# mpuhand2.net
KiCad netlist of a schematic drawn in Altium Designer
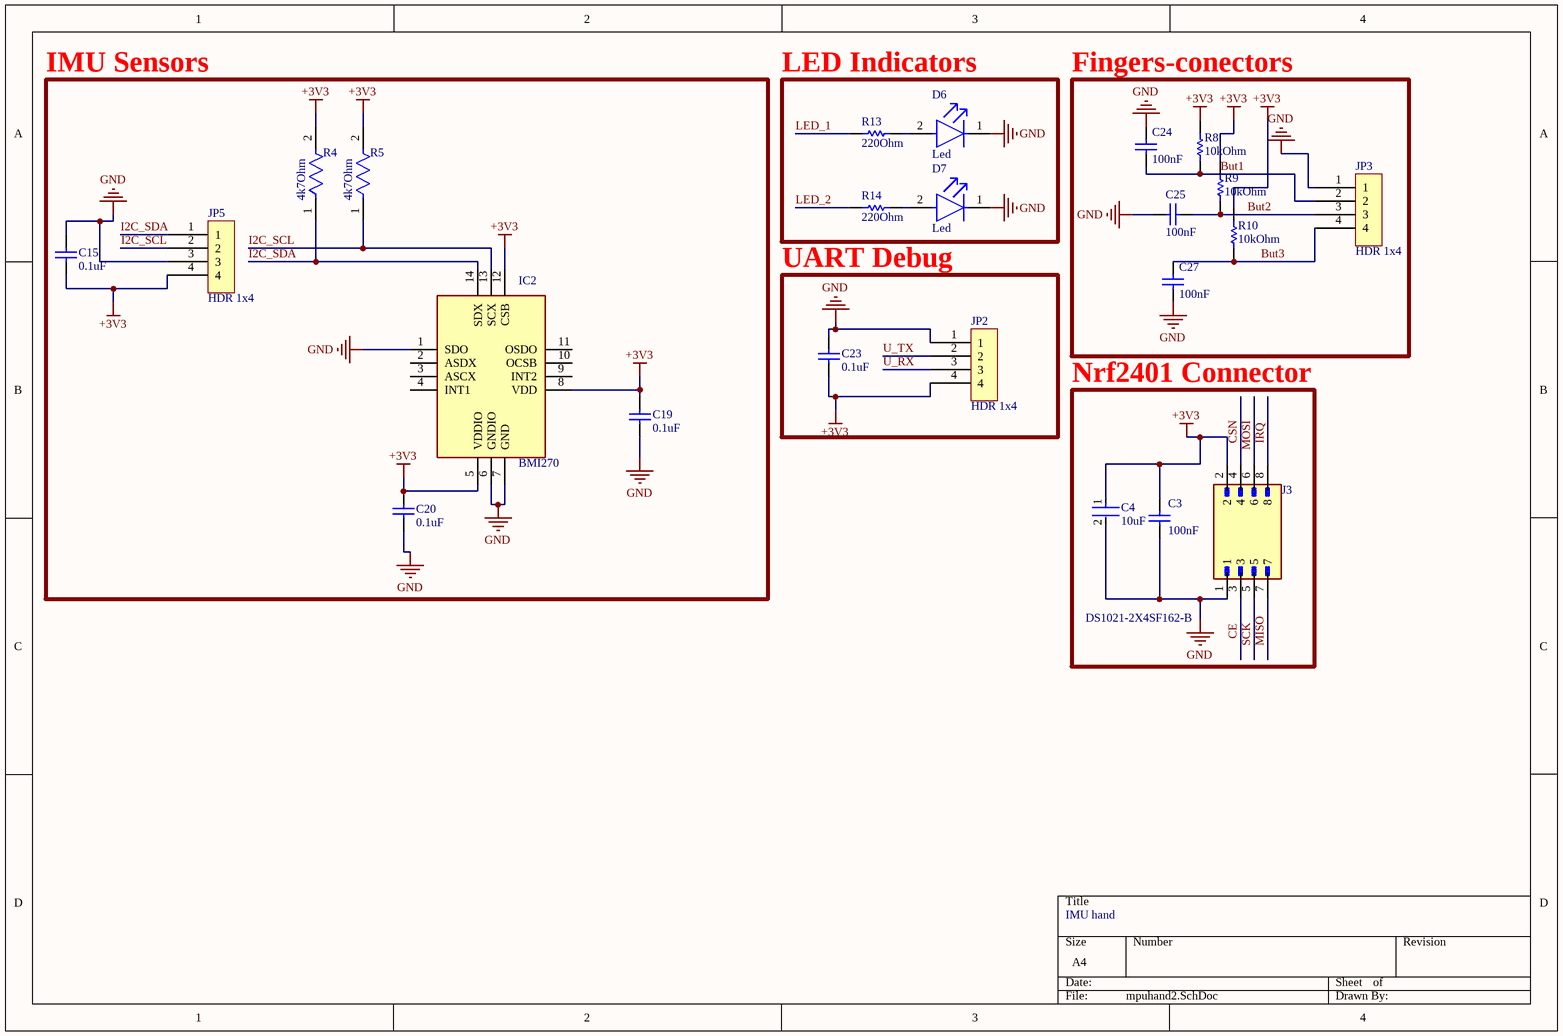
[diagram p0: mpuhand2.SchDoc]

(export (version "E")
  (design (tool "Eeschema 10.0.6"))
  (components
    (comp (ref "C3")
      (value "100nF")
      (footprint "CAPC1050X55X23ML05T13")
      (description "Chip Capacitor, 100 nF, +/- 10%, 16 V, -55 to 125 degC, 0402 (1005 Metric), RoHS, Tape and Reel")
      (fields (field (name "MANUFACTURER") "Samsung Electro-Mechanics"))
      (libsource (lib "Altium Content Vault") (part "CAP-NP-2"))
    )
    (comp (ref "C4")
      (value "10uF")
      (footprint "FP-CL21-IPC_B")
      (description "CL21 Series 0805 10uF 16V ±10% Tolerance X5R Multilayer Ceramic Chip Capacitor")
      (fields (field (name "VOLTAGE") "16V") (field (name "TOLERANCE") "10%"))
      (libsource (lib "Altium Content Vault") (part "b4654b650e69147ec39a6b967a45e02"))
    )
    (comp (ref "C15")
      (value "0.1uF")
      (footprint "CAPC1050X55X23ML05T13")
      (description "Chip Capacitor, 100 nF, +/- 10%, 16 V, -55 to 125 degC, 0402 (1005 Metric), RoHS, Tape and Reel")
      (fields (field (name "MANUFACTURER") "Samsung Electro-Mechanics"))
      (libsource (lib "Altium Content Vault") (part "CAP-NP-2"))
    )
    (comp (ref "C19")
      (value "0.1uF")
      (footprint "CAPC1050X55X23ML05T13")
      (description "Chip Capacitor, 100 nF, +/- 10%, 16 V, -55 to 125 degC, 0402 (1005 Metric), RoHS, Tape and Reel")
      (fields (field (name "MANUFACTURER") "Samsung Electro-Mechanics"))
      (libsource (lib "Altium Content Vault") (part "CAP-NP-2"))
    )
    (comp (ref "C20")
      (value "0.1uF")
      (footprint "CAPC1050X55X23ML05T13")
      (description "Chip Capacitor, 100 nF, +/- 10%, 16 V, -55 to 125 degC, 0402 (1005 Metric), RoHS, Tape and Reel")
      (fields (field (name "MANUFACTURER") "Samsung Electro-Mechanics"))
      (libsource (lib "Altium Content Vault") (part "CAP-NP-2"))
    )
    (comp (ref "C23")
      (value "0.1uF")
      (footprint "CAPC1050X55X23ML05T13")
      (description "Chip Capacitor, 100 nF, +/- 10%, 16 V, -55 to 125 degC, 0402 (1005 Metric), RoHS, Tape and Reel")
      (fields (field (name "MANUFACTURER") "Samsung Electro-Mechanics"))
      (libsource (lib "Altium Content Vault") (part "CAP-NP-2"))
    )
    (comp (ref "C24")
      (value "100nF")
      (footprint "CAPC1050X55X23ML05T13")
      (description "Chip Capacitor, 100 nF, +/- 10%, 16 V, -55 to 125 degC, 0402 (1005 Metric), RoHS, Tape and Reel")
      (fields (field (name "MANUFACTURER") "Samsung Electro-Mechanics"))
      (libsource (lib "Altium Content Vault") (part "CAP-NP-2"))
    )
    (comp (ref "C25")
      (value "100nF")
      (footprint "CAPC1050X55X23ML05T13")
      (description "Chip Capacitor, 100 nF, +/- 10%, 16 V, -55 to 125 degC, 0402 (1005 Metric), RoHS, Tape and Reel")
      (fields (field (name "MANUFACTURER") "Samsung Electro-Mechanics"))
      (libsource (lib "Altium Content Vault") (part "CAP-NP-2"))
    )
    (comp (ref "C27")
      (value "100nF")
      (footprint "CAPC1050X55X23ML05T13")
      (description "Chip Capacitor, 100 nF, +/- 10%, 16 V, -55 to 125 degC, 0402 (1005 Metric), RoHS, Tape and Reel")
      (fields (field (name "MANUFACTURER") "Samsung Electro-Mechanics"))
      (libsource (lib "Altium Content Vault") (part "CAP-NP-2"))
    )
    (comp (ref "D6")
      (value "Led")
      (footprint "FP-LTST-C191GKT-MFG")
      (description "LED GREEN CLEAR CHIP SMD")
      (libsource (lib "Altium Content Vault") (part "8706943c75ba83719d021d2fdc84c58"))
    )
    (comp (ref "D7")
      (value "Led")
      (footprint "FP-LTST-C191GKT-MFG")
      (description "LED GREEN CLEAR CHIP SMD")
      (libsource (lib "Altium Content Vault") (part "8706943c75ba83719d021d2fdc84c58"))
    )
    (comp (ref "IC2")
      (value "BMI270")
      (footprint "SamacSys:BMI270")
      (description "Integrated Circuit")
      (fields (field (name "MOUSER PART NUMBER") "262-BMI270"))
      (libsource (lib "*") (part "BMI270"))
    )
    (comp (ref "J3")
      (value "DS1021-2X4SF162-B")
      (footprint "CONNFLY_DS1021-2X4SF162-B")
      (description "Pin header; pin strips; male; PIN: 8; straight; 2.54mm; THT; 2x4")
      (fields (field (name "MF") "Connfly"))
      (libsource (lib "DS1021-2X4SF162-B") (part "DS1021-2X4SF162-B"))
    )
    (comp (ref "JP2")
      (value "HDR 1x4")
      (footprint "HDR Male1_4 2.54mm")
      (description "CONN HEADER VERT 4POS 2.54MM")
      (fields
        (field (name "MANUFACTURER") "Amphenol FCI")
        (field (name "MANUFACTURER PART NUMBER") "68001-204HLF")
      )
      (libsource (lib "Male_Header_1_4 2.54mm") (part "68001-204HLF"))
    )
    (comp (ref "JP3")
      (value "HDR 1x4")
      (footprint "HDR Male1_4 2.54mm")
      (description "CONN HEADER VERT 4POS 2.54MM")
      (fields
        (field (name "MANUFACTURER") "Amphenol FCI")
        (field (name "MANUFACTURER PART NUMBER") "68001-204HLF")
      )
      (libsource (lib "Male_Header_1_4 2.54mm") (part "68001-204HLF"))
    )
    (comp (ref "JP5")
      (value "HDR 1x4")
      (footprint "HDR Male1_4 2.54mm")
      (description "CONN HEADER VERT 4POS 2.54MM")
      (fields
        (field (name "MANUFACTURER") "Amphenol FCI")
        (field (name "MANUFACTURER PART NUMBER") "68001-204HLF")
      )
      (libsource (lib "Male_Header_1_4 2.54mm") (part "68001-204HLF"))
    )
    (comp (ref "R4")
      (value "4k7Ohm")
      (footprint "FP-RC0402-0_4-MFG")
      (fields (field (name "TOLERANCE") "5%"))
      (libsource (lib "Altium Content Vault") (part "RC0402JR-074K7L"))
    )
    (comp (ref "R5")
      (value "4k7Ohm")
      (footprint "FP-RC0402-0_4-MFG")
      (fields (field (name "TOLERANCE") "5%"))
      (libsource (lib "Altium Content Vault") (part "RC0402JR-074K7L"))
    )
    (comp (ref "R8")
      (value "10kOhm")
      (footprint "RESC2013X60X35ML10T20")
      (description "Chip Resistor, 10 KOhm, +/- 5%, 0.125 W, -55 to 155 degC, 0805 (2012 Metric), RoHS, Tape and Reel")
      (fields (field (name "MANUFACTURER") "Yageo"))
      (libsource (lib "Altium Content Vault") (part "RES-2"))
    )
    (comp (ref "R9")
      (value "10kOhm")
      (footprint "RESC2013X60X35ML10T20")
      (description "Chip Resistor, 10 KOhm, +/- 5%, 0.125 W, -55 to 155 degC, 0805 (2012 Metric), RoHS, Tape and Reel")
      (fields (field (name "MANUFACTURER") "Yageo"))
      (libsource (lib "Altium Content Vault") (part "RES-2"))
    )
    (comp (ref "R10")
      (value "10kOhm")
      (footprint "RESC2013X60X35ML10T20")
      (description "Chip Resistor, 10 KOhm, +/- 5%, 0.125 W, -55 to 155 degC, 0805 (2012 Metric), RoHS, Tape and Reel")
      (fields (field (name "MANUFACTURER") "Yageo"))
      (libsource (lib "Altium Content Vault") (part "RES-2"))
    )
    (comp (ref "R13")
      (value "220Ohm")
      (footprint "RESC1608X55X25ML10T15")
      (libsource (lib "Altium Content Vault") (part "RES-2"))
    )
    (comp (ref "R14")
      (value "220Ohm")
      (footprint "RESC1608X55X25ML10T15")
      (libsource (lib "Altium Content Vault") (part "RES-2"))
    )
  )
  (nets
    (net (code "1") (name "+3V3") (class "Default")
      (node (ref "C15") (pin "1") (pinfunction "1_1") (pintype "passive"))
      (node (ref "C19") (pin "2") (pinfunction "2_2") (pintype "passive"))
      (node (ref "C20") (pin "2") (pinfunction "2_2") (pintype "passive"))
      (node (ref "C23") (pin "1") (pinfunction "1_1") (pintype "passive"))
      (node (ref "C3") (pin "2") (pinfunction "2_2") (pintype "passive"))
      (node (ref "C4") (pin "1") (pinfunction "1_1") (pintype "passive"))
      (node (ref "IC2") (pin "12") (pinfunction "CSB_12") (pintype "passive"))
      (node (ref "IC2") (pin "5") (pinfunction "VDDIO_5") (pintype "passive"))
      (node (ref "IC2") (pin "8") (pinfunction "VDD_8") (pintype "passive"))
      (node (ref "J3") (pin "2") (pinfunction "2_2") (pintype "passive"))
      (node (ref "JP2") (pin "4") (pinfunction "4_4") (pintype "passive"))
      (node (ref "JP5") (pin "4") (pinfunction "4_4") (pintype "passive"))
      (node (ref "R10") (pin "2") (pinfunction "2_2") (pintype "passive"))
      (node (ref "R4") (pin "2") (pinfunction "2_2") (pintype "passive"))
      (node (ref "R5") (pin "2") (pinfunction "2_2") (pintype "passive"))
      (node (ref "R8") (pin "2") (pinfunction "2_2") (pintype "passive"))
      (node (ref "R9") (pin "2") (pinfunction "2_2") (pintype "passive"))
    )
    (net (code "2") (name "/But1") (class "Default")
      (node (ref "C24") (pin "1") (pinfunction "1_1") (pintype "passive"))
      (node (ref "JP3") (pin "2") (pinfunction "2_2") (pintype "passive"))
      (node (ref "R8") (pin "1") (pinfunction "1_1") (pintype "passive"))
    )
    (net (code "3") (name "/But2") (class "Default")
      (node (ref "C25") (pin "2") (pinfunction "2_2") (pintype "passive"))
      (node (ref "JP3") (pin "3") (pinfunction "3_3") (pintype "passive"))
      (node (ref "R9") (pin "1") (pinfunction "1_1") (pintype "passive"))
    )
    (net (code "4") (name "/But3") (class "Default")
      (node (ref "C27") (pin "2") (pinfunction "2_2") (pintype "passive"))
      (node (ref "JP3") (pin "4") (pinfunction "4_4") (pintype "passive"))
      (node (ref "R10") (pin "1") (pinfunction "1_1") (pintype "passive"))
    )
    (net (code "5") (name "/CE") (class "Default")
      (node (ref "J3") (pin "3") (pinfunction "3_3") (pintype "passive"))
    )
    (net (code "6") (name "/CSN") (class "Default")
      (node (ref "J3") (pin "4") (pinfunction "4_4") (pintype "passive"))
    )
    (net (code "7") (name "/I2C_SCL") (class "Default")
      (node (ref "IC2") (pin "13") (pinfunction "SCX_13") (pintype "passive"))
      (node (ref "JP5") (pin "2") (pinfunction "2_2") (pintype "passive"))
      (node (ref "R5") (pin "1") (pinfunction "1_1") (pintype "passive"))
    )
    (net (code "8") (name "/I2C_SDA") (class "Default")
      (node (ref "IC2") (pin "14") (pinfunction "SDX_14") (pintype "passive"))
      (node (ref "JP5") (pin "1") (pinfunction "1_1") (pintype "passive"))
      (node (ref "R4") (pin "1") (pinfunction "1_1") (pintype "passive"))
    )
    (net (code "9") (name "/IRQ") (class "Default")
      (node (ref "J3") (pin "8") (pinfunction "8_8") (pintype "passive"))
    )
    (net (code "10") (name "/LED_1") (class "Default")
      (node (ref "R13") (pin "2") (pinfunction "2_2") (pintype "passive"))
    )
    (net (code "11") (name "/LED_2") (class "Default")
      (node (ref "R14") (pin "2") (pinfunction "2_2") (pintype "passive"))
    )
    (net (code "12") (name "/MISO") (class "Default")
      (node (ref "J3") (pin "7") (pinfunction "7_7") (pintype "passive"))
    )
    (net (code "13") (name "/MOSI") (class "Default")
      (node (ref "J3") (pin "6") (pinfunction "6_6") (pintype "passive"))
    )
    (net (code "14") (name "/SCK") (class "Default")
      (node (ref "J3") (pin "5") (pinfunction "5_5") (pintype "passive"))
    )
    (net (code "15") (name "/U_RX") (class "Default")
      (node (ref "JP2") (pin "3") (pinfunction "3_3") (pintype "passive"))
    )
    (net (code "16") (name "/U_TX") (class "Default")
      (node (ref "JP2") (pin "2") (pinfunction "2_2") (pintype "passive"))
    )
    (net (code "17") (name "GND") (class "Default")
      (node (ref "C15") (pin "2") (pinfunction "2_2") (pintype "passive"))
      (node (ref "C19") (pin "1") (pinfunction "1_1") (pintype "passive"))
      (node (ref "C20") (pin "1") (pinfunction "1_1") (pintype "passive"))
      (node (ref "C23") (pin "2") (pinfunction "2_2") (pintype "passive"))
      (node (ref "C24") (pin "2") (pinfunction "2_2") (pintype "passive"))
      (node (ref "C25") (pin "1") (pinfunction "1_1") (pintype "passive"))
      (node (ref "C27") (pin "1") (pinfunction "1_1") (pintype "passive"))
      (node (ref "C3") (pin "1") (pinfunction "1_1") (pintype "passive"))
      (node (ref "C4") (pin "2") (pinfunction "2_2") (pintype "passive"))
      (node (ref "D6") (pin "1") (pinfunction "C_1") (pintype "passive"))
      (node (ref "D7") (pin "1") (pinfunction "C_1") (pintype "passive"))
      (node (ref "IC2") (pin "1") (pinfunction "SDO_1") (pintype "passive"))
      (node (ref "IC2") (pin "6") (pinfunction "GNDIO_6") (pintype "passive"))
      (node (ref "IC2") (pin "7") (pinfunction "GND_7") (pintype "passive"))
      (node (ref "J3") (pin "1") (pinfunction "1_1") (pintype "passive"))
      (node (ref "JP2") (pin "1") (pinfunction "1_1") (pintype "passive"))
      (node (ref "JP3") (pin "1") (pinfunction "1_1") (pintype "passive"))
      (node (ref "JP5") (pin "3") (pinfunction "3_3") (pintype "passive"))
    )
    (net (code "18") (name "Net-(D6-A)") (class "Default")
      (node (ref "D6") (pin "2") (pinfunction "A_2") (pintype "passive"))
      (node (ref "R13") (pin "1") (pinfunction "1_1") (pintype "passive"))
    )
    (net (code "19") (name "Net-(D7-A)") (class "Default")
      (node (ref "D7") (pin "2") (pinfunction "A_2") (pintype "passive"))
      (node (ref "R14") (pin "1") (pinfunction "1_1") (pintype "passive"))
    )
    (net (code "20") (name "unconnected-(IC2-ASCX-Pad3)") (class "Default")
      (node (ref "IC2") (pin "3") (pinfunction "ASCX_3") (pintype "passive"))
    )
    (net (code "21") (name "unconnected-(IC2-ASDX-Pad2)") (class "Default")
      (node (ref "IC2") (pin "2") (pinfunction "ASDX_2") (pintype "passive"))
    )
    (net (code "22") (name "unconnected-(IC2-INT1-Pad4)") (class "Default")
      (node (ref "IC2") (pin "4") (pinfunction "INT1_4") (pintype "passive"))
    )
    (net (code "23") (name "unconnected-(IC2-INT2-Pad9)") (class "Default")
      (node (ref "IC2") (pin "9") (pinfunction "INT2_9") (pintype "passive"))
    )
    (net (code "24") (name "unconnected-(IC2-OCSB-Pad10)") (class "Default")
      (node (ref "IC2") (pin "10") (pinfunction "OCSB_10") (pintype "passive"))
    )
    (net (code "25") (name "unconnected-(IC2-OSDO-Pad11)") (class "Default")
      (node (ref "IC2") (pin "11") (pinfunction "OSDO_11") (pintype "passive"))
    )
  )
)
